# Dell_Supply_Hack_V1_3.net
KiCad netlist of a schematic drawn in EAGLE
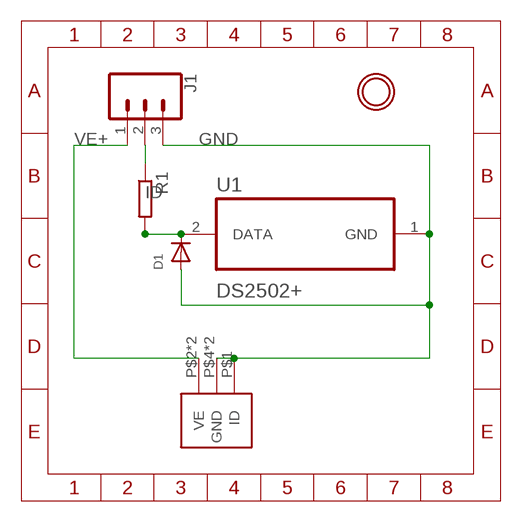
[diagram p0: schematic, sheet 1]

(export (version "E")
  (design (tool "Eeschema 10.0.6"))
  (components
    (comp (ref "D1")
      (value "DIODESOD-323F")
      (footprint "eagle-import:SOD-323F")
      (libsource (lib "eagle-import") (part "DIODESOD-323F"))
    )
    (comp (ref "J1")
      (value "CONN_03LONGPADS")
      (footprint "eagle-import:1X03_LONGPADS")
      (libsource (lib "eagle-import") (part "CONN_03LONGPADS"))
    )
    (comp (ref "R1")
      (value "R-EU_R0603")
      (footprint "eagle-import:R0603")
      (libsource (lib "eagle-import") (part "R-EU_R0603"))
    )
    (comp (ref "U$1")
      (value "DELL_CON")
      (footprint "eagle-import:DELL_CON_01")
      (libsource (lib "eagle-import") (part "DELL_CON"))
    )
    (comp (ref "U$2")
      (value "MOUNTING_HOLE")
      (footprint "eagle-import:MOUNTINGHOLE_3.0_PLATED")
      (libsource (lib "eagle-import") (part "MOUNTING_HOLE"))
    )
    (comp (ref "U1")
      (value "DS2502+")
      (footprint "eagle-import:TO92127P495H695-3")
      (fields (field (name "MF") "Maxim Integrated") (field (name "MP") "DS2502"))
      (libsource (lib "eagle-import") (part "DS2502+"))
    )
  )
  (nets
    (net (code "1") (name "/GND") (class "Default")
      (node (ref "D1") (pin "A") (pinfunction "A_A") (pintype "passive"))
      (node (ref "J1") (pin "3") (pinfunction "3_3") (pintype "passive"))
      (node (ref "U$1") (pin "P$1") (pinfunction "ID_P$1") (pintype "bidirectional"))
      (node (ref "U$1") (pin "P$4") (pinfunction "GND_P$4") (pintype "bidirectional"))
      (node (ref "U$1") (pin "P$5") (pinfunction "GND_P$5") (pintype "bidirectional"))
      (node (ref "U1") (pin "1") (pinfunction "GND_1") (pintype "power_in"))
    )
    (net (code "2") (name "/ID") (class "Default")
      (node (ref "J1") (pin "2") (pinfunction "2_2") (pintype "passive"))
      (node (ref "R1") (pin "1") (pinfunction "1_1") (pintype "passive"))
    )
    (net (code "3") (name "/VE+") (class "Default")
      (node (ref "J1") (pin "1") (pinfunction "1_1") (pintype "passive"))
      (node (ref "U$1") (pin "P$2") (pinfunction "VE_P$2") (pintype "bidirectional"))
      (node (ref "U$1") (pin "P$3") (pinfunction "VE_P$3") (pintype "bidirectional"))
    )
    (net (code "4") (name "Net-(U1-DATA)") (class "Default")
      (node (ref "D1") (pin "C") (pinfunction "C_C") (pintype "passive"))
      (node (ref "R1") (pin "2") (pinfunction "2_2") (pintype "passive"))
      (node (ref "U1") (pin "2") (pinfunction "DATA_2") (pintype "bidirectional"))
    )
  )
)
